# SCH_555-Blinker-board_2025-11-02.net
KiCad netlist of a schematic drawn in EasyEDA
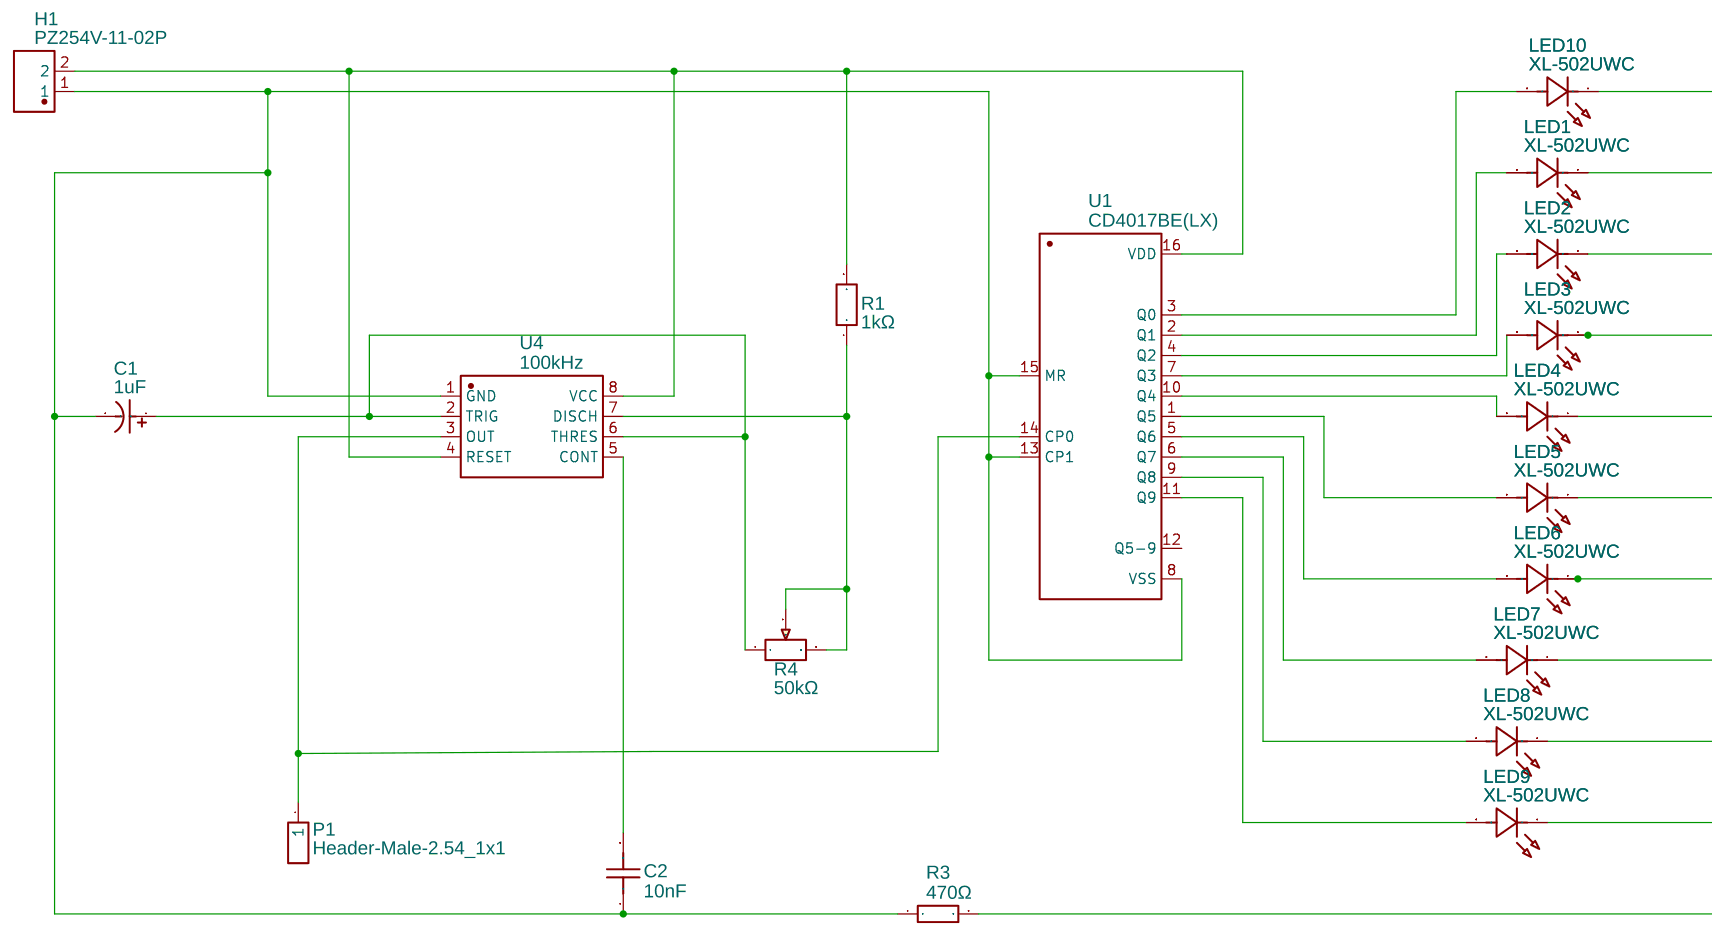
[diagram p0: schematic sheet]

(export (version "E")
  (design (tool "Eeschema 10.0.6"))
  (components
    (comp (ref "C1")
      (value "1uF")
      (fields (field (name "Manufacturer Part") "KF010M050C110A") (field (name "Manufacturer") "CapXon(丰宾)"))
      (libsource (lib "") (part "KF010M050C110A"))
    )
    (comp (ref "C2")
      (value "10nF")
      (fields (field (name "Manufacturer Part") "N09F1B103MN0B0S0N0") (field (name "Manufacturer") "STE(松田)"))
      (libsource (lib "") (part "N09F1B103MN0B0S0N0"))
    )
    (comp (ref "H1")
      (value "PZ254V-11-02P")
      (fields (field (name "Manufacturer") "XFCN(兴飞)"))
      (libsource (lib "") (part "PZ254V-11-02P"))
    )
    (comp (ref "LED1")
      (value "XL-502UWC")
      (fields (field (name "Manufacturer") "XINGLIGHT(成兴光)"))
      (libsource (lib "") (part "XL-502UWC"))
    )
    (comp (ref "LED2")
      (value "XL-502UWC")
      (fields (field (name "Manufacturer") "XINGLIGHT(成兴光)"))
      (libsource (lib "") (part "XL-502UWC"))
    )
    (comp (ref "LED3")
      (value "XL-502UWC")
      (fields (field (name "Manufacturer") "XINGLIGHT(成兴光)"))
      (libsource (lib "") (part "XL-502UWC"))
    )
    (comp (ref "LED4")
      (value "XL-502UWC")
      (fields (field (name "Manufacturer") "XINGLIGHT(成兴光)"))
      (libsource (lib "") (part "XL-502UWC"))
    )
    (comp (ref "LED5")
      (value "XL-502UWC")
      (fields (field (name "Manufacturer") "XINGLIGHT(成兴光)"))
      (libsource (lib "") (part "XL-502UWC"))
    )
    (comp (ref "LED6")
      (value "XL-502UWC")
      (fields (field (name "Manufacturer") "XINGLIGHT(成兴光)"))
      (libsource (lib "") (part "XL-502UWC"))
    )
    (comp (ref "LED7")
      (value "XL-502UWC")
      (fields (field (name "Manufacturer") "XINGLIGHT(成兴光)"))
      (libsource (lib "") (part "XL-502UWC"))
    )
    (comp (ref "LED8")
      (value "XL-502UWC")
      (fields (field (name "Manufacturer") "XINGLIGHT(成兴光)"))
      (libsource (lib "") (part "XL-502UWC"))
    )
    (comp (ref "LED9")
      (value "XL-502UWC")
      (fields (field (name "Manufacturer") "XINGLIGHT(成兴光)"))
      (libsource (lib "") (part "XL-502UWC"))
    )
    (comp (ref "LED10")
      (value "XL-502UWC")
      (fields (field (name "Manufacturer") "XINGLIGHT(成兴光)"))
      (libsource (lib "") (part "XL-502UWC"))
    )
    (comp (ref "P1")
      (value "Header-Male-2.54_1x1")
      (fields (field (name "Manufacturer Part") "2.54-1*1P针") (field (name "Manufacturer") "BOOMELE(博穆精密)"))
      (libsource (lib "") (part "Header-Male-2.54_1x1"))
    )
    (comp (ref "R1")
      (value "1kΩ")
      (fields (field (name "Manufacturer Part") "MF1/4W-1KΩ±1%T52") (field (name "Manufacturer") "华星机电"))
      (libsource (lib "") (part "MF1/4W-1KΩ±1%T52"))
    )
    (comp (ref "R3")
      (value "470Ω")
      (fields
        (field (name "Manufacturer Part") "MFR0W4F4700A50")
        (field (name "Manufacturer") "UNI-ROYAL(厚声)")
      )
      (libsource (lib "") (part "MFR0W4F4700A50"))
    )
    (comp (ref "R4")
      (value "50kΩ")
      (fields (field (name "Manufacturer Part") "3296X-1-503") (field (name "Manufacturer") "BOCHEN(博晨)"))
      (libsource (lib "") (part "3296X-1-503_C118912"))
    )
    (comp (ref "U1")
      (value "CD4017BE(LX)")
      (fields (field (name "Manufacturer") "LX(灵星芯微)"))
      (libsource (lib "") (part "CD4017BE(LX)"))
    )
    (comp (ref "U4")
      (value "100kHz")
      (fields (field (name "Manufacturer Part") "NE555P") (field (name "Manufacturer") "TI(德州仪器)"))
      (libsource (lib "") (part "NE555P"))
    )
  )
  (nets
    (net (code "1") (name "Net-(LED1-A)") (class "Default")
      (node (ref "LED1") (pin "2") (pinfunction "A_2") (pintype "unspecified"))
      (node (ref "U1") (pin "2") (pinfunction "Q1_2") (pintype "unspecified"))
    )
    (net (code "2") (name "Net-(LED1-K)") (class "Default")
      (node (ref "LED1") (pin "1") (pinfunction "K_1") (pintype "unspecified"))
      (node (ref "LED10") (pin "1") (pinfunction "K_1") (pintype "unspecified"))
      (node (ref "LED2") (pin "1") (pinfunction "K_1") (pintype "unspecified"))
      (node (ref "LED3") (pin "1") (pinfunction "K_1") (pintype "unspecified"))
      (node (ref "LED4") (pin "1") (pinfunction "K_1") (pintype "unspecified"))
      (node (ref "LED5") (pin "1") (pinfunction "K_1") (pintype "unspecified"))
      (node (ref "LED6") (pin "1") (pinfunction "K_1") (pintype "unspecified"))
      (node (ref "LED7") (pin "1") (pinfunction "K_1") (pintype "unspecified"))
      (node (ref "LED8") (pin "1") (pinfunction "K_1") (pintype "unspecified"))
      (node (ref "LED9") (pin "1") (pinfunction "K_1") (pintype "unspecified"))
      (node (ref "R3") (pin "2") (pinfunction "2_2") (pintype "input"))
    )
    (net (code "3") (name "Net-(LED2-A)") (class "Default")
      (node (ref "LED2") (pin "2") (pinfunction "A_2") (pintype "unspecified"))
      (node (ref "U1") (pin "4") (pinfunction "Q2_4") (pintype "unspecified"))
    )
    (net (code "4") (name "Net-(LED3-A)") (class "Default")
      (node (ref "LED3") (pin "2") (pinfunction "A_2") (pintype "unspecified"))
      (node (ref "U1") (pin "7") (pinfunction "Q3_7") (pintype "unspecified"))
    )
    (net (code "5") (name "Net-(LED4-A)") (class "Default")
      (node (ref "LED4") (pin "2") (pinfunction "A_2") (pintype "unspecified"))
      (node (ref "U1") (pin "10") (pinfunction "Q4_10") (pintype "unspecified"))
    )
    (net (code "6") (name "Net-(LED5-A)") (class "Default")
      (node (ref "LED5") (pin "2") (pinfunction "A_2") (pintype "unspecified"))
      (node (ref "U1") (pin "1") (pinfunction "Q5_1") (pintype "unspecified"))
    )
    (net (code "7") (name "Net-(LED6-A)") (class "Default")
      (node (ref "LED6") (pin "2") (pinfunction "A_2") (pintype "unspecified"))
      (node (ref "U1") (pin "5") (pinfunction "Q6_5") (pintype "unspecified"))
    )
    (net (code "8") (name "Net-(LED7-A)") (class "Default")
      (node (ref "LED7") (pin "2") (pinfunction "A_2") (pintype "unspecified"))
      (node (ref "U1") (pin "6") (pinfunction "Q7_6") (pintype "unspecified"))
    )
    (net (code "9") (name "Net-(LED8-A)") (class "Default")
      (node (ref "LED8") (pin "2") (pinfunction "A_2") (pintype "unspecified"))
      (node (ref "U1") (pin "9") (pinfunction "Q8_9") (pintype "unspecified"))
    )
    (net (code "10") (name "Net-(LED9-A)") (class "Default")
      (node (ref "LED9") (pin "2") (pinfunction "A_2") (pintype "unspecified"))
      (node (ref "U1") (pin "11") (pinfunction "Q9_11") (pintype "unspecified"))
    )
    (net (code "11") (name "Net-(LED10-A)") (class "Default")
      (node (ref "LED10") (pin "2") (pinfunction "A_2") (pintype "unspecified"))
      (node (ref "U1") (pin "3") (pinfunction "Q0_3") (pintype "unspecified"))
    )
    (net (code "12") (name "Net-(U1-CP0)") (class "Default")
      (node (ref "P1") (pin "1") (pinfunction "1_1") (pintype "input"))
      (node (ref "U1") (pin "14") (pinfunction "CP0_14") (pintype "unspecified"))
      (node (ref "U4") (pin "3") (pinfunction "OUT_3") (pintype "unspecified"))
    )
    (net (code "13") (name "Net-(U1-CP1)") (class "Default")
      (node (ref "C1") (pin "2") (pinfunction "2_2") (pintype "input"))
      (node (ref "C2") (pin "1") (pinfunction "1_1") (pintype "unspecified"))
      (node (ref "H1") (pin "1") (pinfunction "1_1") (pintype "unspecified"))
      (node (ref "R3") (pin "1") (pinfunction "1_1") (pintype "input"))
      (node (ref "U1") (pin "13") (pinfunction "CP1_13") (pintype "unspecified"))
      (node (ref "U1") (pin "15") (pinfunction "MR_15") (pintype "unspecified"))
      (node (ref "U1") (pin "8") (pinfunction "VSS_8") (pintype "unspecified"))
      (node (ref "U4") (pin "1") (pinfunction "GND_1") (pintype "unspecified"))
    )
    (net (code "14") (name "Net-(U1-VDD)") (class "Default")
      (node (ref "H1") (pin "2") (pinfunction "2_2") (pintype "unspecified"))
      (node (ref "R1") (pin "2") (pinfunction "2_2") (pintype "unspecified"))
      (node (ref "U1") (pin "16") (pinfunction "VDD_16") (pintype "unspecified"))
      (node (ref "U4") (pin "4") (pinfunction "RESET_4") (pintype "unspecified"))
      (node (ref "U4") (pin "8") (pinfunction "VCC_8") (pintype "unspecified"))
    )
    (net (code "15") (name "Net-(U4-CONT)") (class "Default")
      (node (ref "C2") (pin "2") (pinfunction "2_2") (pintype "unspecified"))
      (node (ref "U4") (pin "5") (pinfunction "CONT_5") (pintype "unspecified"))
    )
    (net (code "16") (name "Net-(U4-DISCH)") (class "Default")
      (node (ref "R1") (pin "1") (pinfunction "1_1") (pintype "unspecified"))
      (node (ref "R4") (pin "2") (pinfunction "2_2") (pintype "input"))
      (node (ref "R4") (pin "3") (pinfunction "3_3") (pintype "input"))
      (node (ref "U4") (pin "7") (pinfunction "DISCH_7") (pintype "unspecified"))
    )
    (net (code "17") (name "Net-(U4-THRES)") (class "Default")
      (node (ref "C1") (pin "1") (pinfunction "1_1") (pintype "input"))
      (node (ref "R4") (pin "1") (pinfunction "1_1") (pintype "input"))
      (node (ref "U4") (pin "2") (pinfunction "TRIG_2") (pintype "unspecified"))
      (node (ref "U4") (pin "6") (pinfunction "THRES_6") (pintype "unspecified"))
    )
    (net (code "18") (name "unconnected-(U1-Q5-9-Pad12)") (class "Default")
      (node (ref "U1") (pin "12") (pinfunction "Q5-9_12") (pintype "unspecified"))
    )
  )
)
